# Sensor-LED.net
KiCad netlist of a schematic drawn in Altium Designer
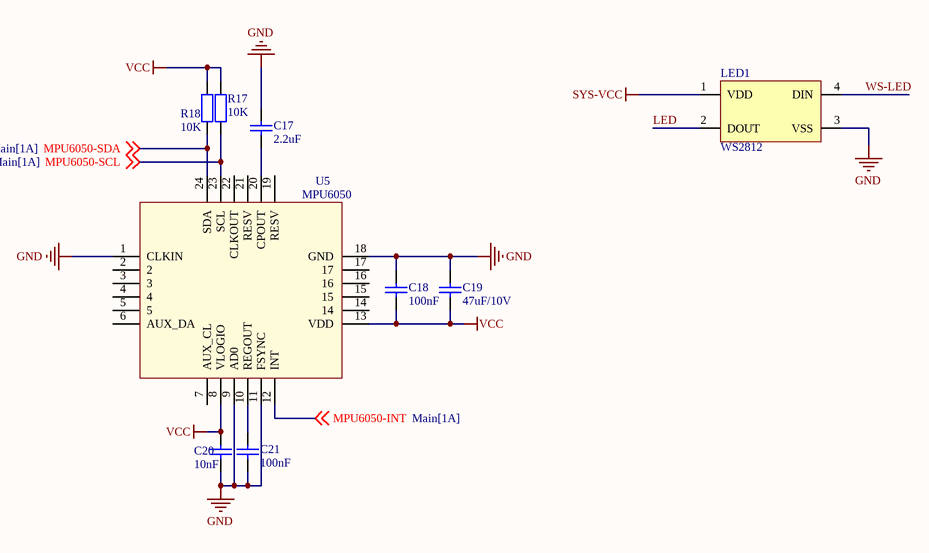
[diagram p0: Sensor-LED.SchDoc]

(export (version "E")
  (design (tool "Eeschema 10.0.6"))
  (components
    (comp (ref "C17")
      (value "2.2uF")
      (footprint "C0402_M")
      (description "贴片电容/MLCC电容")
      (libsource (lib "0.1 - 电阻-电容-电感-晶振-晶体-磁珠-电位器-法拉电容-馈通电容") (part "C"))
    )
    (comp (ref "C18")
      (value "100nF")
      (footprint "C0402_M")
      (description "贴片电容/MLCC电容")
      (libsource (lib "0.1 - 电阻-电容-电感-晶振-晶体-磁珠-电位器-法拉电容-馈通电容") (part "C"))
    )
    (comp (ref "C19")
      (value "47uF/10V")
      (footprint "C0402_M")
      (description "贴片电容/MLCC电容")
      (libsource (lib "0.1 - 电阻-电容-电感-晶振-晶体-磁珠-电位器-法拉电容-馈通电容") (part "C"))
    )
    (comp (ref "C20")
      (value "10nF")
      (footprint "C0402_M")
      (description "贴片电容/MLCC电容")
      (libsource (lib "0.1 - 电阻-电容-电感-晶振-晶体-磁珠-电位器-法拉电容-馈通电容") (part "C"))
    )
    (comp (ref "C21")
      (value "100nF")
      (footprint "C0402_M")
      (description "贴片电容/MLCC电容")
      (libsource (lib "0.1 - 电阻-电容-电感-晶振-晶体-磁珠-电位器-法拉电容-馈通电容") (part "C"))
    )
    (comp (ref "LED1")
      (value "WS2812")
      (footprint "LED 3535")
      (libsource (lib "0.3 - LED发光二极管-IR二极管_接收管-光耦") (part "WS2812"))
    )
    (comp (ref "R17")
      (value "10K")
      (footprint "R0402_M")
      (description "贴片电阻")
      (libsource (lib "0.1 - 电阻-电容-电感-晶振-晶体-磁珠-电位器-法拉电容-馈通电容") (part "R"))
    )
    (comp (ref "R18")
      (value "10K")
      (footprint "R0402_M")
      (description "贴片电阻")
      (libsource (lib "0.1 - 电阻-电容-电感-晶振-晶体-磁珠-电位器-法拉电容-馈通电容") (part "R"))
    )
    (comp (ref "U5")
      (value "MPU6050")
      (footprint "QFN24 4x4_M")
      (description "三轴加速度+三轴陀螺仪")
      (libsource (lib "0.9 - 传感器-存储器-模块") (part "MPU6050"))
    )
  )
  (nets
    (net (code "1") (name "/LED") (class "Default")
      (node (ref "LED1") (pin "2") (pinfunction "DOUT_2") (pintype "passive"))
    )
    (net (code "2") (name "/WS-LED") (class "Default")
      (node (ref "LED1") (pin "4") (pinfunction "DIN_4") (pintype "passive"))
    )
    (net (code "3") (name "GND") (class "Default")
      (node (ref "C17") (pin "2") (pinfunction "2_2") (pintype "passive"))
      (node (ref "C18") (pin "2") (pinfunction "2_2") (pintype "passive"))
      (node (ref "C19") (pin "2") (pinfunction "2_2") (pintype "passive"))
      (node (ref "C20") (pin "1") (pinfunction "1_1") (pintype "passive"))
      (node (ref "C21") (pin "1") (pinfunction "1_1") (pintype "passive"))
      (node (ref "LED1") (pin "3") (pinfunction "VSS_3") (pintype "passive"))
      (node (ref "U5") (pin "1") (pinfunction "CLKIN_1") (pintype "passive"))
      (node (ref "U5") (pin "11") (pinfunction "FSYNC_11") (pintype "passive"))
      (node (ref "U5") (pin "18") (pinfunction "GND_18") (pintype "passive"))
      (node (ref "U5") (pin "9") (pinfunction "AD0_9") (pintype "passive"))
    )
    (net (code "4") (name "MPU6050-INT") (class "Default")
      (node (ref "U5") (pin "12") (pinfunction "INT_12") (pintype "passive"))
    )
    (net (code "5") (name "MPU6050-SCL") (class "Default")
      (node (ref "R17") (pin "2") (pinfunction "2_2") (pintype "passive"))
      (node (ref "U5") (pin "23") (pinfunction "SCL_23") (pintype "passive"))
    )
    (net (code "6") (name "MPU6050-SDA") (class "Default")
      (node (ref "R18") (pin "2") (pinfunction "2_2") (pintype "passive"))
      (node (ref "U5") (pin "24") (pinfunction "SDA_24") (pintype "passive"))
    )
    (net (code "7") (name "Net-(U5-CPOUT)") (class "Default")
      (node (ref "C17") (pin "1") (pinfunction "1_1") (pintype "passive"))
      (node (ref "U5") (pin "20") (pinfunction "CPOUT_20") (pintype "passive"))
    )
    (net (code "8") (name "Net-(U5-REGOUT)") (class "Default")
      (node (ref "C21") (pin "2") (pinfunction "2_2") (pintype "passive"))
      (node (ref "U5") (pin "10") (pinfunction "REGOUT_10") (pintype "passive"))
    )
    (net (code "9") (name "SYS-VCC") (class "Default")
      (node (ref "LED1") (pin "1") (pinfunction "VDD_1") (pintype "passive"))
    )
    (net (code "10") (name "VCC") (class "Default")
      (node (ref "C18") (pin "1") (pinfunction "1_1") (pintype "passive"))
      (node (ref "C19") (pin "1") (pinfunction "1_1") (pintype "passive"))
      (node (ref "C20") (pin "2") (pinfunction "2_2") (pintype "passive"))
      (node (ref "R17") (pin "1") (pinfunction "1_1") (pintype "passive"))
      (node (ref "R18") (pin "1") (pinfunction "1_1") (pintype "passive"))
      (node (ref "U5") (pin "13") (pinfunction "VDD_13") (pintype "passive"))
      (node (ref "U5") (pin "8") (pinfunction "VLOGIO_8") (pintype "passive"))
    )
    (net (code "11") (name "unconnected-(U5-AUX_CL-Pad7)") (class "Default")
      (node (ref "U5") (pin "7") (pinfunction "AUX_CL_7") (pintype "passive"))
    )
    (net (code "12") (name "unconnected-(U5-AUX_DA-Pad6)") (class "Default")
      (node (ref "U5") (pin "6") (pinfunction "AUX_DA_6") (pintype "passive"))
    )
    (net (code "13") (name "unconnected-(U5-CLKOUT-Pad22)") (class "Default")
      (node (ref "U5") (pin "22") (pinfunction "CLKOUT_22") (pintype "passive"))
    )
    (net (code "14") (name "unconnected-(U5-Pad2)") (class "Default")
      (node (ref "U5") (pin "2") (pinfunction "2_2") (pintype "passive"))
    )
    (net (code "15") (name "unconnected-(U5-Pad3)") (class "Default")
      (node (ref "U5") (pin "3") (pinfunction "3_3") (pintype "passive"))
    )
    (net (code "16") (name "unconnected-(U5-Pad4)") (class "Default")
      (node (ref "U5") (pin "4") (pinfunction "4_4") (pintype "passive"))
    )
    (net (code "17") (name "unconnected-(U5-Pad5)") (class "Default")
      (node (ref "U5") (pin "5") (pinfunction "5_5") (pintype "passive"))
    )
    (net (code "18") (name "unconnected-(U5-Pad14)") (class "Default")
      (node (ref "U5") (pin "14") (pinfunction "14_14") (pintype "passive"))
    )
    (net (code "19") (name "unconnected-(U5-Pad15)") (class "Default")
      (node (ref "U5") (pin "15") (pinfunction "15_15") (pintype "passive"))
    )
    (net (code "20") (name "unconnected-(U5-Pad16)") (class "Default")
      (node (ref "U5") (pin "16") (pinfunction "16_16") (pintype "passive"))
    )
    (net (code "21") (name "unconnected-(U5-Pad17)") (class "Default")
      (node (ref "U5") (pin "17") (pinfunction "17_17") (pintype "passive"))
    )
    (net (code "22") (name "unconnected-(U5-RESV-Pad19)") (class "Default")
      (node (ref "U5") (pin "19") (pinfunction "RESV_19") (pintype "passive"))
    )
    (net (code "23") (name "unconnected-(U5-RESV-Pad21)") (class "Default")
      (node (ref "U5") (pin "21") (pinfunction "RESV_21") (pintype "passive"))
    )
  )
)
